# ADMP441_BreakoutBoard.net
KiCad netlist of a schematic drawn in EAGLE
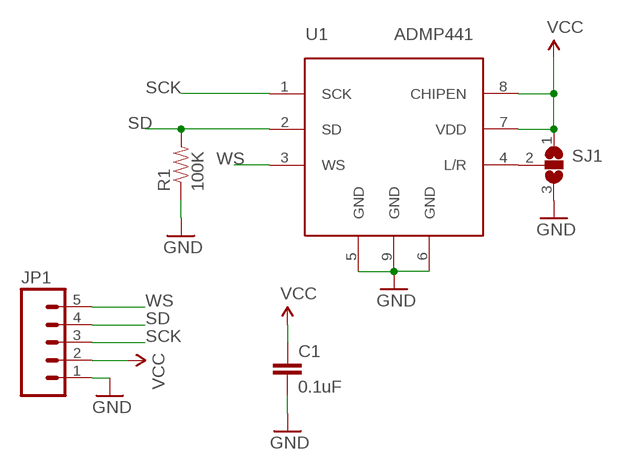
[diagram p0: schematic, sheet 1]

(export (version "E")
  (design (tool "Eeschema 10.0.6"))
  (components
    (comp (ref "C1")
      (value "0.1uF")
      (footprint "eagle-import:0603-CAP")
      (libsource (lib "eagle-import") (part "CAP0603-CAP"))
    )
    (comp (ref "JP1")
      (value "M05PTH")
      (footprint "eagle-import:1X05")
      (libsource (lib "eagle-import") (part "M05PTH"))
    )
    (comp (ref "R1")
      (value "100K")
      (footprint "eagle-import:0603-RES")
      (libsource (lib "eagle-import") (part "RESISTOR0603-RES"))
    )
    (comp (ref "SJ1")
      (value "SJ2W")
      (footprint "eagle-import:SJ_2")
      (libsource (lib "eagle-import") (part "SJ2W"))
    )
    (comp (ref "U1")
      (value "ADMP441")
      (footprint "eagle-import:ADMP441")
      (libsource (lib "eagle-import") (part "ADMP441"))
    )
  )
  (nets
    (net (code "1") (name "/SCK") (class "Default")
      (node (ref "JP1") (pin "3") (pinfunction "3_3") (pintype "passive"))
      (node (ref "U1") (pin "1") (pinfunction "SCK_1") (pintype "bidirectional"))
    )
    (net (code "2") (name "/SD") (class "Default")
      (node (ref "JP1") (pin "4") (pinfunction "4_4") (pintype "passive"))
      (node (ref "R1") (pin "2") (pinfunction "2_2") (pintype "passive"))
      (node (ref "U1") (pin "2") (pinfunction "SD_2") (pintype "bidirectional"))
    )
    (net (code "3") (name "/WS") (class "Default")
      (node (ref "JP1") (pin "5") (pinfunction "5_5") (pintype "passive"))
      (node (ref "U1") (pin "3") (pinfunction "WS_3") (pintype "bidirectional"))
    )
    (net (code "4") (name "GND") (class "Default")
      (node (ref "C1") (pin "2") (pinfunction "2_2") (pintype "passive"))
      (node (ref "JP1") (pin "1") (pinfunction "1_1") (pintype "passive"))
      (node (ref "R1") (pin "1") (pinfunction "1_1") (pintype "passive"))
      (node (ref "SJ1") (pin "3") (pinfunction "3_3") (pintype "passive"))
      (node (ref "U1") (pin "5") (pinfunction "GND_5") (pintype "bidirectional"))
      (node (ref "U1") (pin "6") (pinfunction "GND_6") (pintype "bidirectional"))
      (node (ref "U1") (pin "9") (pinfunction "GND_9") (pintype "bidirectional"))
    )
    (net (code "5") (name "Net-(U1-L{slash}R)") (class "Default")
      (node (ref "SJ1") (pin "2") (pinfunction "2_2") (pintype "passive"))
      (node (ref "U1") (pin "4") (pinfunction "L/R_4") (pintype "bidirectional"))
    )
    (net (code "6") (name "VCC") (class "Default")
      (node (ref "C1") (pin "1") (pinfunction "1_1") (pintype "passive"))
      (node (ref "JP1") (pin "2") (pinfunction "2_2") (pintype "passive"))
      (node (ref "SJ1") (pin "1") (pinfunction "1_1") (pintype "passive"))
      (node (ref "U1") (pin "7") (pinfunction "VDD_7") (pintype "bidirectional"))
      (node (ref "U1") (pin "8") (pinfunction "CHIPEN_8") (pintype "bidirectional"))
    )
  )
)
